# RemoteHardware.net
KiCad netlist of a schematic drawn in EAGLE
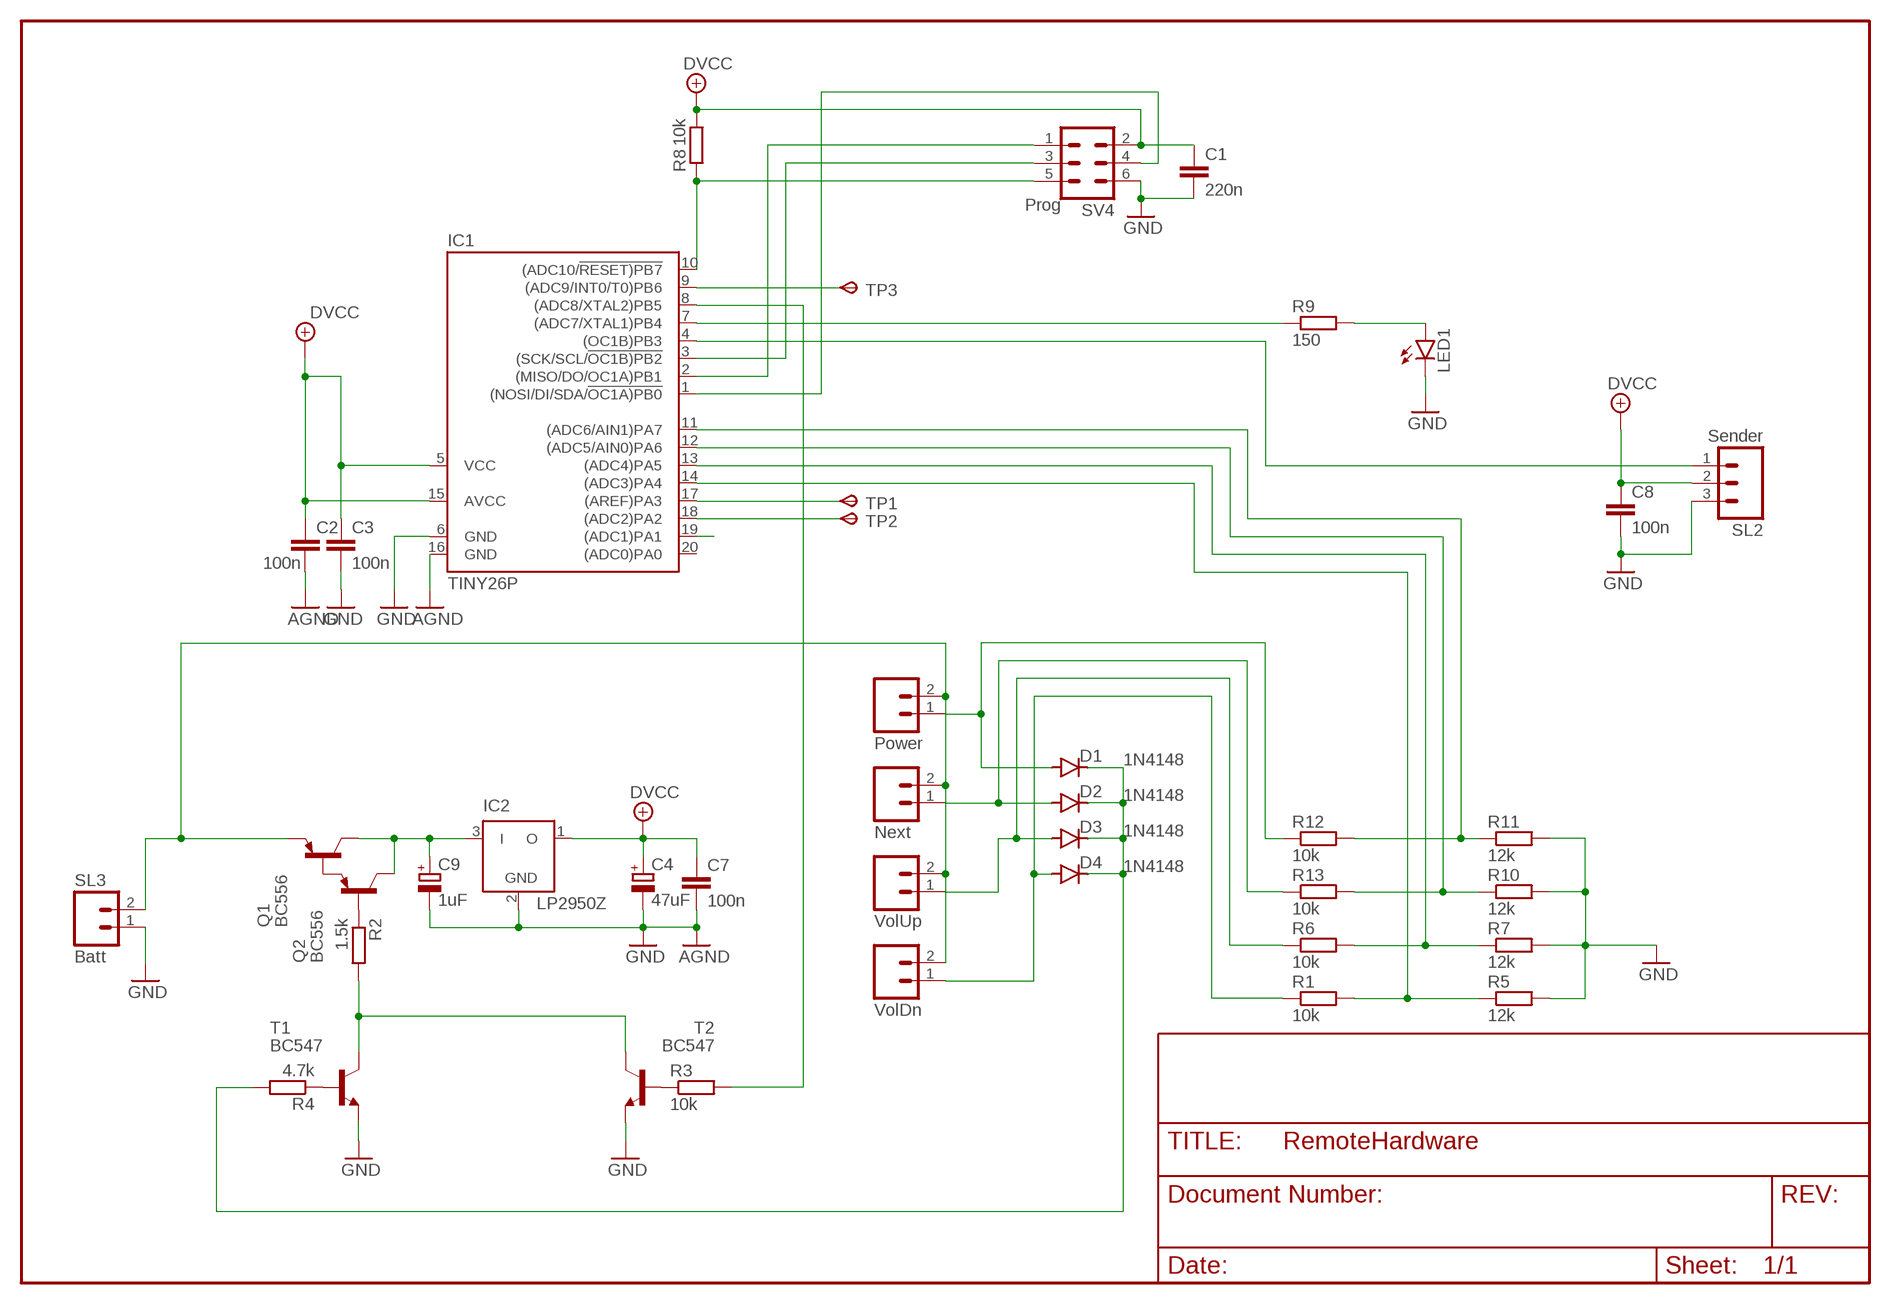
[diagram p0: schematic, sheet 1]

(export (version "E")
  (design (tool "Eeschema 10.0.6"))
  (components
    (comp (ref "C1")
      (value "220n")
      (footprint "eagle-import:C025-024X044")
      (libsource (lib "eagle-import") (part "C-EU025-024X044"))
    )
    (comp (ref "C2")
      (value "100n")
      (footprint "eagle-import:C025-024X044")
      (libsource (lib "eagle-import") (part "C-EU025-024X044"))
    )
    (comp (ref "C3")
      (value "100n")
      (footprint "eagle-import:C025-024X044")
      (libsource (lib "eagle-import") (part "C-EU025-024X044"))
    )
    (comp (ref "C4")
      (value "47uF")
      (footprint "eagle-import:E2,5-6")
      (libsource (lib "eagle-import") (part "CPOL-EUE2.5-6"))
    )
    (comp (ref "C7")
      (value "100n")
      (footprint "eagle-import:C025-024X044")
      (libsource (lib "eagle-import") (part "C-EU025-024X044"))
    )
    (comp (ref "C8")
      (value "100n")
      (footprint "eagle-import:C025-024X044")
      (libsource (lib "eagle-import") (part "C-EU025-024X044"))
    )
    (comp (ref "C9")
      (value "1uF")
      (footprint "eagle-import:E2,5-6")
      (libsource (lib "eagle-import") (part "CPOL-EUE2.5-6"))
    )
    (comp (ref "D1")
      (value "1N4148")
      (footprint "eagle-import:D-5")
      (libsource (lib "eagle-import") (part "DIODE-D-5"))
    )
    (comp (ref "D2")
      (value "1N4148")
      (footprint "eagle-import:D-5")
      (libsource (lib "eagle-import") (part "DIODE-D-5"))
    )
    (comp (ref "D3")
      (value "1N4148")
      (footprint "eagle-import:D-5")
      (libsource (lib "eagle-import") (part "DIODE-D-5"))
    )
    (comp (ref "D4")
      (value "1N4148")
      (footprint "eagle-import:D-5")
      (libsource (lib "eagle-import") (part "DIODE-D-5"))
    )
    (comp (ref "IC1")
      (value "TINY26P")
      (footprint "eagle-import:DIL20")
      (libsource (lib "eagle-import") (part "TINY26P"))
    )
    (comp (ref "IC2")
      (value "LP2950Z")
      (footprint "eagle-import:TO92")
      (libsource (lib "eagle-import") (part "LP2950Z"))
    )
    (comp (ref "LED1")
      (value "LED3MM")
      (footprint "eagle-import:LED3MM")
      (libsource (lib "eagle-import") (part "LED3MM"))
    )
    (comp (ref "Q1")
      (value "BC556")
      (footprint "eagle-import:TO92-EBC")
      (libsource (lib "eagle-import") (part "BC556"))
    )
    (comp (ref "Q2")
      (value "BC556")
      (footprint "eagle-import:TO92-EBC")
      (libsource (lib "eagle-import") (part "BC556"))
    )
    (comp (ref "R1")
      (value "10k")
      (footprint "eagle-import:0204_5")
      (libsource (lib "eagle-import") (part "R-EU_0204/5"))
    )
    (comp (ref "R2")
      (value "1.5k")
      (footprint "eagle-import:0204_5")
      (libsource (lib "eagle-import") (part "R-EU_0204/5"))
    )
    (comp (ref "R3")
      (value "10k")
      (footprint "eagle-import:0204_5")
      (libsource (lib "eagle-import") (part "R-EU_0204/5"))
    )
    (comp (ref "R4")
      (value "4.7k")
      (footprint "eagle-import:0204_5")
      (libsource (lib "eagle-import") (part "R-EU_0204/5"))
    )
    (comp (ref "R5")
      (value "12k")
      (footprint "eagle-import:0204_5")
      (libsource (lib "eagle-import") (part "R-EU_0204/5"))
    )
    (comp (ref "R6")
      (value "10k")
      (footprint "eagle-import:0204_5")
      (libsource (lib "eagle-import") (part "R-EU_0204/5"))
    )
    (comp (ref "R7")
      (value "12k")
      (footprint "eagle-import:0204_5")
      (libsource (lib "eagle-import") (part "R-EU_0204/5"))
    )
    (comp (ref "R8")
      (value "10k")
      (footprint "eagle-import:0204_5")
      (libsource (lib "eagle-import") (part "R-EU_0204/5"))
    )
    (comp (ref "R9")
      (value "150")
      (footprint "eagle-import:0204_5")
      (libsource (lib "eagle-import") (part "R-EU_0204/5"))
    )
    (comp (ref "R10")
      (value "12k")
      (footprint "eagle-import:0204_5")
      (libsource (lib "eagle-import") (part "R-EU_0204/5"))
    )
    (comp (ref "R11")
      (value "12k")
      (footprint "eagle-import:0204_5")
      (libsource (lib "eagle-import") (part "R-EU_0204/5"))
    )
    (comp (ref "R12")
      (value "10k")
      (footprint "eagle-import:0204_5")
      (libsource (lib "eagle-import") (part "R-EU_0204/5"))
    )
    (comp (ref "R13")
      (value "10k")
      (footprint "eagle-import:0204_5")
      (libsource (lib "eagle-import") (part "R-EU_0204/5"))
    )
    (comp (ref "SL1")
      (value "Power")
      (footprint "eagle-import:02P")
      (libsource (lib "eagle-import") (part "M02"))
    )
    (comp (ref "SL2")
      (value "Sender")
      (footprint "eagle-import:03P")
      (libsource (lib "eagle-import") (part "M03"))
    )
    (comp (ref "SL3")
      (value "Batt")
      (footprint "eagle-import:02P")
      (libsource (lib "eagle-import") (part "M02"))
    )
    (comp (ref "SL4")
      (value "Next")
      (footprint "eagle-import:02P")
      (libsource (lib "eagle-import") (part "M02"))
    )
    (comp (ref "SL5")
      (value "VolUp")
      (footprint "eagle-import:02P")
      (libsource (lib "eagle-import") (part "M02"))
    )
    (comp (ref "SL6")
      (value "VolDn")
      (footprint "eagle-import:02P")
      (libsource (lib "eagle-import") (part "M02"))
    )
    (comp (ref "SV4")
      (value "Prog")
      (footprint "eagle-import:MA03-2")
      (libsource (lib "eagle-import") (part "MA03-2"))
    )
    (comp (ref "T1")
      (value "BC547")
      (footprint "eagle-import:TO92")
      (libsource (lib "eagle-import") (part "BC547"))
    )
    (comp (ref "T2")
      (value "BC547")
      (footprint "eagle-import:TO92")
      (libsource (lib "eagle-import") (part "BC547"))
    )
    (comp (ref "TP1")
      (value "TPSB1,27")
      (footprint "eagle-import:B1,27")
      (libsource (lib "eagle-import") (part "TPSB1,27"))
    )
    (comp (ref "TP2")
      (value "TPSB1,27")
      (footprint "eagle-import:B1,27")
      (libsource (lib "eagle-import") (part "TPSB1,27"))
    )
    (comp (ref "TP3")
      (value "TPSB1,27")
      (footprint "eagle-import:B1,27")
      (libsource (lib "eagle-import") (part "TPSB1,27"))
    )
  )
  (nets
    (net (code "1") (name "AGND") (class "Default")
      (node (ref "C1") (pin "2") (pinfunction "2_2") (pintype "passive"))
      (node (ref "C2") (pin "2") (pinfunction "2_2") (pintype "passive"))
      (node (ref "C3") (pin "2") (pinfunction "2_2") (pintype "passive"))
      (node (ref "C4") (pin "-") (pinfunction "-_-") (pintype "passive"))
      (node (ref "C7") (pin "2") (pinfunction "2_2") (pintype "passive"))
      (node (ref "C8") (pin "2") (pinfunction "2_2") (pintype "passive"))
      (node (ref "C9") (pin "-") (pinfunction "-_-") (pintype "passive"))
      (node (ref "IC1") (pin "16") (pinfunction "GND_16") (pintype "power_in"))
      (node (ref "IC1") (pin "6") (pinfunction "GND_6") (pintype "power_in"))
      (node (ref "IC2") (pin "2") (pinfunction "GND_2") (pintype "power_in"))
      (node (ref "LED1") (pin "K") (pinfunction "C_K") (pintype "passive"))
      (node (ref "R10") (pin "2") (pinfunction "2_2") (pintype "passive"))
      (node (ref "R11") (pin "2") (pinfunction "2_2") (pintype "passive"))
      (node (ref "R5") (pin "2") (pinfunction "2_2") (pintype "passive"))
      (node (ref "R7") (pin "2") (pinfunction "2_2") (pintype "passive"))
      (node (ref "SL2") (pin "3") (pinfunction "3_3") (pintype "passive"))
      (node (ref "SL3") (pin "1") (pinfunction "1_1") (pintype "passive"))
      (node (ref "SV4") (pin "6") (pinfunction "6_6") (pintype "passive"))
      (node (ref "T1") (pin "1") (pinfunction "E_1") (pintype "passive"))
      (node (ref "T2") (pin "1") (pinfunction "E_1") (pintype "passive"))
    )
    (net (code "2") (name "DVCC") (class "Default")
      (node (ref "C1") (pin "1") (pinfunction "1_1") (pintype "passive"))
      (node (ref "C2") (pin "1") (pinfunction "1_1") (pintype "passive"))
      (node (ref "C3") (pin "1") (pinfunction "1_1") (pintype "passive"))
      (node (ref "C4") (pin "+") (pinfunction "+_+") (pintype "passive"))
      (node (ref "C7") (pin "1") (pinfunction "1_1") (pintype "passive"))
      (node (ref "C8") (pin "1") (pinfunction "1_1") (pintype "passive"))
      (node (ref "IC1") (pin "15") (pinfunction "AVCC_15") (pintype "power_in"))
      (node (ref "IC1") (pin "5") (pinfunction "VCC_5") (pintype "power_in"))
      (node (ref "IC2") (pin "1") (pinfunction "O_1") (pintype "input"))
      (node (ref "R8") (pin "2") (pinfunction "2_2") (pintype "passive"))
      (node (ref "SL2") (pin "2") (pinfunction "2_2") (pintype "passive"))
      (node (ref "SV4") (pin "2") (pinfunction "2_2") (pintype "passive"))
    )
    (net (code "3") (name "Net-(D1-PadA)") (class "Default")
      (node (ref "D1") (pin "A") (pinfunction "A_A") (pintype "passive"))
      (node (ref "R12") (pin "1") (pinfunction "1_1") (pintype "passive"))
      (node (ref "SL1") (pin "1") (pinfunction "1_1") (pintype "passive"))
    )
    (net (code "4") (name "Net-(D1-PadC)") (class "Default")
      (node (ref "D1") (pin "C") (pinfunction "C_C") (pintype "passive"))
      (node (ref "D2") (pin "C") (pinfunction "C_C") (pintype "passive"))
      (node (ref "D3") (pin "C") (pinfunction "C_C") (pintype "passive"))
      (node (ref "D4") (pin "C") (pinfunction "C_C") (pintype "passive"))
      (node (ref "R4") (pin "2") (pinfunction "2_2") (pintype "passive"))
    )
    (net (code "5") (name "Net-(D2-PadA)") (class "Default")
      (node (ref "D2") (pin "A") (pinfunction "A_A") (pintype "passive"))
      (node (ref "R13") (pin "1") (pinfunction "1_1") (pintype "passive"))
      (node (ref "SL4") (pin "1") (pinfunction "1_1") (pintype "passive"))
    )
    (net (code "6") (name "Net-(D3-PadA)") (class "Default")
      (node (ref "D3") (pin "A") (pinfunction "A_A") (pintype "passive"))
      (node (ref "R6") (pin "1") (pinfunction "1_1") (pintype "passive"))
      (node (ref "SL5") (pin "1") (pinfunction "1_1") (pintype "passive"))
    )
    (net (code "7") (name "Net-(D4-PadA)") (class "Default")
      (node (ref "D4") (pin "A") (pinfunction "A_A") (pintype "passive"))
      (node (ref "R1") (pin "1") (pinfunction "1_1") (pintype "passive"))
      (node (ref "SL6") (pin "1") (pinfunction "1_1") (pintype "passive"))
    )
    (net (code "8") (name "Net-(IC1-(ADC2)PA2)") (class "Default")
      (node (ref "IC1") (pin "18") (pinfunction "(ADC2)PA2_18") (pintype "bidirectional"))
      (node (ref "TP2") (pin "TP") (pinfunction "PP_TP") (pintype "input"))
    )
    (net (code "9") (name "Net-(IC1-(ADC3)PA4)") (class "Default")
      (node (ref "IC1") (pin "14") (pinfunction "(ADC3)PA4_14") (pintype "bidirectional"))
      (node (ref "R1") (pin "2") (pinfunction "2_2") (pintype "passive"))
      (node (ref "R5") (pin "1") (pinfunction "1_1") (pintype "passive"))
    )
    (net (code "10") (name "Net-(IC1-(ADC4)PA5)") (class "Default")
      (node (ref "IC1") (pin "13") (pinfunction "(ADC4)PA5_13") (pintype "bidirectional"))
      (node (ref "R6") (pin "2") (pinfunction "2_2") (pintype "passive"))
      (node (ref "R7") (pin "1") (pinfunction "1_1") (pintype "passive"))
    )
    (net (code "11") (name "Net-(IC1-(ADC5{slash}AIN0)PA6)") (class "Default")
      (node (ref "IC1") (pin "12") (pinfunction "(ADC5/AIN0)PA6_12") (pintype "bidirectional"))
      (node (ref "R10") (pin "1") (pinfunction "1_1") (pintype "passive"))
      (node (ref "R13") (pin "2") (pinfunction "2_2") (pintype "passive"))
    )
    (net (code "12") (name "Net-(IC1-(ADC6{slash}AIN1)PA7)") (class "Default")
      (node (ref "IC1") (pin "11") (pinfunction "(ADC6/AIN1)PA7_11") (pintype "bidirectional"))
      (node (ref "R11") (pin "1") (pinfunction "1_1") (pintype "passive"))
      (node (ref "R12") (pin "2") (pinfunction "2_2") (pintype "passive"))
    )
    (net (code "13") (name "Net-(IC1-(ADC7{slash}XTAL1)PB4)") (class "Default")
      (node (ref "IC1") (pin "7") (pinfunction "(ADC7/XTAL1)PB4_7") (pintype "bidirectional"))
      (node (ref "R9") (pin "1") (pinfunction "1_1") (pintype "passive"))
    )
    (net (code "14") (name "Net-(IC1-(ADC8{slash}XTAL2)PB5)") (class "Default")
      (node (ref "IC1") (pin "8") (pinfunction "(ADC8/XTAL2)PB5_8") (pintype "bidirectional"))
      (node (ref "R3") (pin "2") (pinfunction "2_2") (pintype "passive"))
    )
    (net (code "15") (name "Net-(IC1-(ADC9{slash}INT0{slash}T0)PB6)") (class "Default")
      (node (ref "IC1") (pin "9") (pinfunction "(ADC9/INT0/T0)PB6_9") (pintype "bidirectional"))
      (node (ref "TP3") (pin "TP") (pinfunction "PP_TP") (pintype "input"))
    )
    (net (code "16") (name "Net-(IC1-(ADC10{slash}~{RESET})PB7)") (class "Default")
      (node (ref "IC1") (pin "10") (pinfunction "(ADC10/~{RESET})PB7_10") (pintype "bidirectional"))
      (node (ref "R8") (pin "1") (pinfunction "1_1") (pintype "passive"))
      (node (ref "SV4") (pin "5") (pinfunction "5_5") (pintype "passive"))
    )
    (net (code "17") (name "Net-(IC1-(AREF)PA3)") (class "Default")
      (node (ref "IC1") (pin "17") (pinfunction "(AREF)PA3_17") (pintype "bidirectional"))
      (node (ref "TP1") (pin "TP") (pinfunction "PP_TP") (pintype "input"))
    )
    (net (code "18") (name "Net-(IC1-(MISO{slash}DO{slash}OC1A)PB1)") (class "Default")
      (node (ref "IC1") (pin "2") (pinfunction "(MISO/DO/OC1A)PB1_2") (pintype "bidirectional"))
      (node (ref "SV4") (pin "1") (pinfunction "1_1") (pintype "passive"))
    )
    (net (code "19") (name "Net-(IC1-(NOSI{slash}DI{slash}SDA{slash}~{OC1A})PB0)") (class "Default")
      (node (ref "IC1") (pin "1") (pinfunction "(NOSI/DI/SDA/~{OC1A})PB0_1") (pintype "bidirectional"))
      (node (ref "SV4") (pin "4") (pinfunction "4_4") (pintype "passive"))
    )
    (net (code "20") (name "Net-(IC1-(OC1B)PB3)") (class "Default")
      (node (ref "IC1") (pin "4") (pinfunction "(OC1B)PB3_4") (pintype "bidirectional"))
      (node (ref "SL2") (pin "1") (pinfunction "1_1") (pintype "passive"))
    )
    (net (code "21") (name "Net-(IC1-(SCK{slash}SCL{slash}~{OC1B})PB2)") (class "Default")
      (node (ref "IC1") (pin "3") (pinfunction "(SCK/SCL/~{OC1B})PB2_3") (pintype "bidirectional"))
      (node (ref "SV4") (pin "3") (pinfunction "3_3") (pintype "passive"))
    )
    (net (code "22") (name "Net-(IC2-I)") (class "Default")
      (node (ref "C9") (pin "+") (pinfunction "+_+") (pintype "passive"))
      (node (ref "IC2") (pin "3") (pinfunction "I_3") (pintype "input"))
      (node (ref "Q1") (pin "C") (pinfunction "C_C") (pintype "passive"))
      (node (ref "Q2") (pin "C") (pinfunction "C_C") (pintype "passive"))
    )
    (net (code "23") (name "Net-(LED1-PadA)") (class "Default")
      (node (ref "LED1") (pin "A") (pinfunction "A_A") (pintype "passive"))
      (node (ref "R9") (pin "2") (pinfunction "2_2") (pintype "passive"))
    )
    (net (code "24") (name "Net-(Q1-PadB)") (class "Default")
      (node (ref "Q1") (pin "B") (pinfunction "B_B") (pintype "passive"))
      (node (ref "Q2") (pin "E") (pinfunction "E_E") (pintype "passive"))
    )
    (net (code "25") (name "Net-(Q1-PadE)") (class "Default")
      (node (ref "Q1") (pin "E") (pinfunction "E_E") (pintype "passive"))
      (node (ref "SL1") (pin "2") (pinfunction "2_2") (pintype "passive"))
      (node (ref "SL3") (pin "2") (pinfunction "2_2") (pintype "passive"))
      (node (ref "SL4") (pin "2") (pinfunction "2_2") (pintype "passive"))
      (node (ref "SL5") (pin "2") (pinfunction "2_2") (pintype "passive"))
      (node (ref "SL6") (pin "2") (pinfunction "2_2") (pintype "passive"))
    )
    (net (code "26") (name "Net-(Q2-PadB)") (class "Default")
      (node (ref "Q2") (pin "B") (pinfunction "B_B") (pintype "passive"))
      (node (ref "R2") (pin "1") (pinfunction "1_1") (pintype "passive"))
    )
    (net (code "27") (name "Net-(T1-B)") (class "Default")
      (node (ref "R4") (pin "1") (pinfunction "1_1") (pintype "passive"))
      (node (ref "T1") (pin "2") (pinfunction "B_2") (pintype "passive"))
    )
    (net (code "28") (name "Net-(T1-C)") (class "Default")
      (node (ref "R2") (pin "2") (pinfunction "2_2") (pintype "passive"))
      (node (ref "T1") (pin "3") (pinfunction "C_3") (pintype "passive"))
      (node (ref "T2") (pin "3") (pinfunction "C_3") (pintype "passive"))
    )
    (net (code "29") (name "Net-(T2-B)") (class "Default")
      (node (ref "R3") (pin "1") (pinfunction "1_1") (pintype "passive"))
      (node (ref "T2") (pin "2") (pinfunction "B_2") (pintype "passive"))
    )
    (net (code "30") (name "unconnected-(IC1-(ADC0)PA0-Pad20)") (class "Default")
      (node (ref "IC1") (pin "20") (pinfunction "(ADC0)PA0_20") (pintype "bidirectional"))
    )
    (net (code "31") (name "unconnected-(IC1-(ADC1)PA1-Pad19)") (class "Default")
      (node (ref "IC1") (pin "19") (pinfunction "(ADC1)PA1_19") (pintype "bidirectional"))
    )
  )
)
